# schematic.net
KiCad netlist of a schematic drawn in Altium Designer
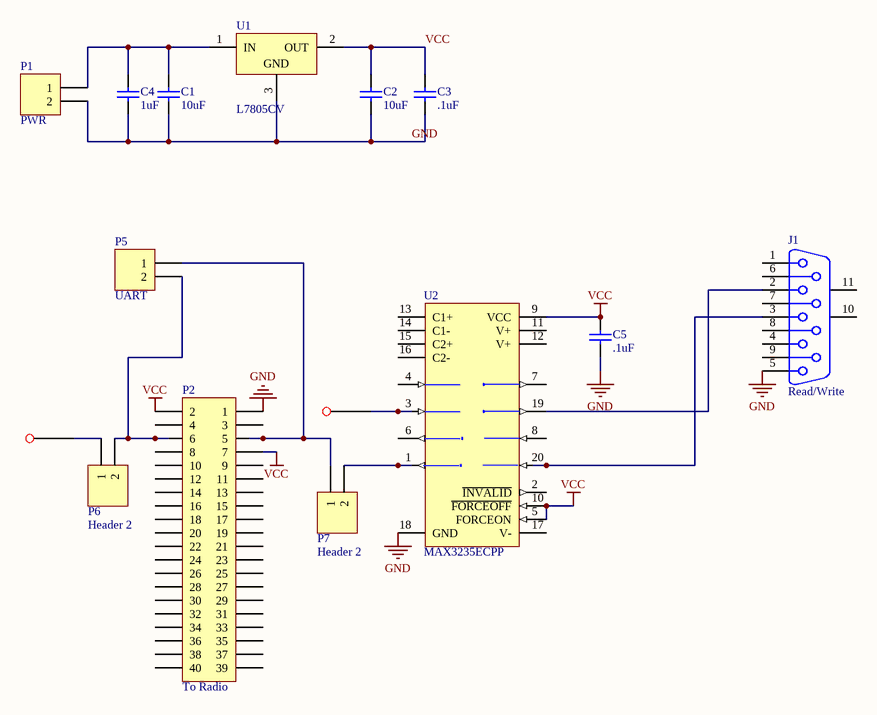
[diagram p0: schematic.SchDoc]

(export (version "E")
  (design (tool "Eeschema 10.0.6"))
  (components
    (comp (ref "C1")
      (value "10uF")
      (footprint "1206")
      (description "Capacitor")
      (fields (field (name "PUBLISHER") "Altium Limited"))
      (libsource (lib "Miscellaneous Devices") (part "Cap"))
    )
    (comp (ref "C2")
      (value "10uF")
      (footprint "1206")
      (description "Capacitor")
      (fields (field (name "PUBLISHER") "Altium Limited"))
      (libsource (lib "Miscellaneous Devices") (part "Cap"))
    )
    (comp (ref "C3")
      (value ".1uF")
      (footprint "1206")
      (description "Capacitor")
      (fields (field (name "PUBLISHER") "Altium Limited"))
      (libsource (lib "Miscellaneous Devices") (part "Cap"))
    )
    (comp (ref "C4")
      (value "1uF")
      (footprint "1206")
      (description "Capacitor")
      (fields (field (name "PUBLISHER") "Altium Limited"))
      (libsource (lib "Miscellaneous Devices") (part "Cap"))
    )
    (comp (ref "C5")
      (value ".1uF")
      (footprint "1206")
      (description "Capacitor")
      (fields (field (name "PUBLISHER") "Altium Limited"))
      (libsource (lib "Miscellaneous Devices") (part "Cap"))
    )
    (comp (ref "J1")
      (value "Read/Write")
      (footprint "DE-9")
      (description "Receptacle Assembly, 9 Position, Right Angle")
      (fields (field (name "PUBLISHER") "Altium Limited"))
      (libsource (lib "Miscellaneous Connectors") (part "D Connector 9"))
    )
    (comp (ref "P1")
      (value "PWR")
      (footprint "Screw Terminal - 2")
      (description "Header, 2-Pin")
      (fields (field (name "PUBLISHER") "Altium Limited"))
      (libsource (lib "Miscellaneous Connectors") (part "Header 2"))
    )
    (comp (ref "P2")
      (value "To Radio")
      (footprint "Header 2x20 2mm r&c pitch")
      (description "Header, 20-Pin, Dual row")
      (fields (field (name "PUBLISHER") "Altium Limited"))
      (libsource (lib "Miscellaneous Connectors") (part "Header 20X2"))
    )
    (comp (ref "P3")
      (value "~")
      (footprint "Solder Pad")
      (description "A pad to solder a wire connection to")
      (libsource (lib "schLib") (part "Solder Pad"))
    )
    (comp (ref "P4")
      (value "~")
      (footprint "Solder Pad")
      (description "A pad to solder a wire connection to")
      (libsource (lib "schLib") (part "Solder Pad"))
    )
    (comp (ref "P5")
      (value "UART")
      (footprint "Screw Terminal - 2")
      (description "Header, 2-Pin")
      (fields (field (name "PUBLISHER") "Altium Limited"))
      (libsource (lib "Miscellaneous Connectors") (part "Header 2"))
    )
    (comp (ref "P6")
      (value "Header 2")
      (footprint "HDR1X2")
      (description "Header, 2-Pin")
      (fields (field (name "PUBLISHER") "Altium Limited"))
      (libsource (lib "") (part "Header 2_1"))
    )
    (comp (ref "P7")
      (value "Header 2")
      (footprint "HDR1X2")
      (description "Header, 2-Pin")
      (fields (field (name "PUBLISHER") "Altium Limited"))
      (libsource (lib "") (part "Header 2_1"))
    )
    (comp (ref "U1")
      (value "L7805CV")
      (footprint "TO220ABN")
      (description "Positive Voltage Regulator")
      (fields (field (name "PUBLISHER") "Altium Limited"))
      (libsource (lib "ST Power Mgt Voltage Regulator") (part "L7805CV"))
    )
    (comp (ref "U2")
      (value "MAX3235ECPP")
      (footprint "PP20")
      (description "±15kV ESD-Protected, 1µA, 250kbps, 5V, Dual RS-232 Transceiver with Internal Capacitor")
      (fields (field (name "PUBLISHER") "Altium Limited"))
      (libsource (lib "Maxim Communication Transceiver") (part "MAX3235ECPP"))
    )
  )
  (nets
    (net (code "1") (name "GND") (class "Default")
      (node (ref "C1") (pin "1") (pinfunction "1_1") (pintype "passive"))
      (node (ref "C2") (pin "1") (pinfunction "1_1") (pintype "passive"))
      (node (ref "C3") (pin "1") (pinfunction "1_1") (pintype "passive"))
      (node (ref "C4") (pin "1") (pinfunction "1_1") (pintype "passive"))
      (node (ref "C5") (pin "1") (pinfunction "1_1") (pintype "passive"))
      (node (ref "J1") (pin "5") (pinfunction "5_5") (pintype "passive"))
      (node (ref "P1") (pin "2") (pinfunction "2_2") (pintype "passive"))
      (node (ref "P2") (pin "1") (pinfunction "1_1") (pintype "passive"))
      (node (ref "U1") (pin "3") (pinfunction "GND_3") (pintype "power_in"))
      (node (ref "U2") (pin "18") (pinfunction "GND_18") (pintype "power_in"))
    )
    (net (code "2") (name "Net-(P2-Pad5)") (class "Default")
      (node (ref "P2") (pin "5") (pinfunction "5_5") (pintype "passive"))
      (node (ref "P5") (pin "1") (pinfunction "1_1") (pintype "passive"))
      (node (ref "P7") (pin "1") (pinfunction "1_1") (pintype "passive"))
    )
    (net (code "3") (name "Net-(P2-Pad6)") (class "Default")
      (node (ref "P2") (pin "6") (pinfunction "6_6") (pintype "passive"))
      (node (ref "P5") (pin "2") (pinfunction "2_2") (pintype "passive"))
      (node (ref "P6") (pin "2") (pinfunction "2_2") (pintype "passive"))
    )
    (net (code "4") (name "Net-(P3-Pad1)") (class "Default")
      (node (ref "P3") (pin "1") (pinfunction "1_1") (pintype "passive"))
      (node (ref "P6") (pin "1") (pinfunction "1_1") (pintype "passive"))
    )
    (net (code "5") (name "Net-(U1-IN)") (class "Default")
      (node (ref "C1") (pin "2") (pinfunction "2_2") (pintype "passive"))
      (node (ref "C4") (pin "2") (pinfunction "2_2") (pintype "passive"))
      (node (ref "P1") (pin "1") (pinfunction "1_1") (pintype "passive"))
      (node (ref "U1") (pin "1") (pinfunction "IN_1") (pintype "power_in"))
    )
    (net (code "6") (name "Net-(U2-R2IN)") (class "Default")
      (node (ref "J1") (pin "3") (pinfunction "3_3") (pintype "passive"))
      (node (ref "U2") (pin "20") (pinfunction "R2IN_20") (pintype "input"))
    )
    (net (code "7") (name "Net-(U2-R2OUT)") (class "Default")
      (node (ref "P7") (pin "2") (pinfunction "2_2") (pintype "passive"))
      (node (ref "U2") (pin "1") (pinfunction "R2OUT_1") (pintype "output"))
    )
    (net (code "8") (name "Net-(U2-T2IN)") (class "Default")
      (node (ref "P4") (pin "1") (pinfunction "1_1") (pintype "passive"))
      (node (ref "U2") (pin "3") (pinfunction "T2IN_3") (pintype "input"))
    )
    (net (code "9") (name "Net-(U2-T2OUT)") (class "Default")
      (node (ref "J1") (pin "2") (pinfunction "2_2") (pintype "passive"))
      (node (ref "U2") (pin "19") (pinfunction "T2OUT_19") (pintype "output"))
    )
    (net (code "10") (name "VCC") (class "Default")
      (node (ref "C2") (pin "2") (pinfunction "2_2") (pintype "passive"))
      (node (ref "C3") (pin "2") (pinfunction "2_2") (pintype "passive"))
      (node (ref "C5") (pin "2") (pinfunction "2_2") (pintype "passive"))
      (node (ref "P2") (pin "2") (pinfunction "2_2") (pintype "passive"))
      (node (ref "P2") (pin "7") (pinfunction "7_7") (pintype "passive"))
      (node (ref "U1") (pin "2") (pinfunction "OUT_2") (pintype "power_in"))
      (node (ref "U2") (pin "10") (pinfunction "~{FORCEOFF}_10") (pintype "input"))
      (node (ref "U2") (pin "5") (pinfunction "FORCEON_5") (pintype "input"))
      (node (ref "U2") (pin "9") (pinfunction "VCC_9") (pintype "power_in"))
    )
    (net (code "11") (name "unconnected-(J1-MH1-Pad10)") (class "Default")
      (node (ref "J1") (pin "10") (pinfunction "MH1_10") (pintype "passive"))
    )
    (net (code "12") (name "unconnected-(J1-MH2-Pad11)") (class "Default")
      (node (ref "J1") (pin "11") (pinfunction "MH2_11") (pintype "passive"))
    )
    (net (code "13") (name "unconnected-(J1-Pad1)") (class "Default")
      (node (ref "J1") (pin "1") (pinfunction "1_1") (pintype "passive"))
    )
    (net (code "14") (name "unconnected-(J1-Pad4)") (class "Default")
      (node (ref "J1") (pin "4") (pinfunction "4_4") (pintype "passive"))
    )
    (net (code "15") (name "unconnected-(J1-Pad6)") (class "Default")
      (node (ref "J1") (pin "6") (pinfunction "6_6") (pintype "passive"))
    )
    (net (code "16") (name "unconnected-(J1-Pad7)") (class "Default")
      (node (ref "J1") (pin "7") (pinfunction "7_7") (pintype "passive"))
    )
    (net (code "17") (name "unconnected-(J1-Pad8)") (class "Default")
      (node (ref "J1") (pin "8") (pinfunction "8_8") (pintype "passive"))
    )
    (net (code "18") (name "unconnected-(J1-Pad9)") (class "Default")
      (node (ref "J1") (pin "9") (pinfunction "9_9") (pintype "passive"))
    )
    (net (code "19") (name "unconnected-(P2-Pad3)") (class "Default")
      (node (ref "P2") (pin "3") (pinfunction "3_3") (pintype "passive"))
    )
    (net (code "20") (name "unconnected-(P2-Pad4)") (class "Default")
      (node (ref "P2") (pin "4") (pinfunction "4_4") (pintype "passive"))
    )
    (net (code "21") (name "unconnected-(P2-Pad8)") (class "Default")
      (node (ref "P2") (pin "8") (pinfunction "8_8") (pintype "passive"))
    )
    (net (code "22") (name "unconnected-(P2-Pad9)") (class "Default")
      (node (ref "P2") (pin "9") (pinfunction "9_9") (pintype "passive"))
    )
    (net (code "23") (name "unconnected-(P2-Pad10)") (class "Default")
      (node (ref "P2") (pin "10") (pinfunction "10_10") (pintype "passive"))
    )
    (net (code "24") (name "unconnected-(P2-Pad11)") (class "Default")
      (node (ref "P2") (pin "11") (pinfunction "11_11") (pintype "passive"))
    )
    (net (code "25") (name "unconnected-(P2-Pad12)") (class "Default")
      (node (ref "P2") (pin "12") (pinfunction "12_12") (pintype "passive"))
    )
    (net (code "26") (name "unconnected-(P2-Pad13)") (class "Default")
      (node (ref "P2") (pin "13") (pinfunction "13_13") (pintype "passive"))
    )
    (net (code "27") (name "unconnected-(P2-Pad14)") (class "Default")
      (node (ref "P2") (pin "14") (pinfunction "14_14") (pintype "passive"))
    )
    (net (code "28") (name "unconnected-(P2-Pad15)") (class "Default")
      (node (ref "P2") (pin "15") (pinfunction "15_15") (pintype "passive"))
    )
    (net (code "29") (name "unconnected-(P2-Pad16)") (class "Default")
      (node (ref "P2") (pin "16") (pinfunction "16_16") (pintype "passive"))
    )
    (net (code "30") (name "unconnected-(P2-Pad17)") (class "Default")
      (node (ref "P2") (pin "17") (pinfunction "17_17") (pintype "passive"))
    )
    (net (code "31") (name "unconnected-(P2-Pad18)") (class "Default")
      (node (ref "P2") (pin "18") (pinfunction "18_18") (pintype "passive"))
    )
    (net (code "32") (name "unconnected-(P2-Pad19)") (class "Default")
      (node (ref "P2") (pin "19") (pinfunction "19_19") (pintype "passive"))
    )
    (net (code "33") (name "unconnected-(P2-Pad20)") (class "Default")
      (node (ref "P2") (pin "20") (pinfunction "20_20") (pintype "passive"))
    )
    (net (code "34") (name "unconnected-(P2-Pad21)") (class "Default")
      (node (ref "P2") (pin "21") (pinfunction "21_21") (pintype "passive"))
    )
    (net (code "35") (name "unconnected-(P2-Pad22)") (class "Default")
      (node (ref "P2") (pin "22") (pinfunction "22_22") (pintype "passive"))
    )
    (net (code "36") (name "unconnected-(P2-Pad23)") (class "Default")
      (node (ref "P2") (pin "23") (pinfunction "23_23") (pintype "passive"))
    )
    (net (code "37") (name "unconnected-(P2-Pad24)") (class "Default")
      (node (ref "P2") (pin "24") (pinfunction "24_24") (pintype "passive"))
    )
    (net (code "38") (name "unconnected-(P2-Pad25)") (class "Default")
      (node (ref "P2") (pin "25") (pinfunction "25_25") (pintype "passive"))
    )
    (net (code "39") (name "unconnected-(P2-Pad26)") (class "Default")
      (node (ref "P2") (pin "26") (pinfunction "26_26") (pintype "passive"))
    )
    (net (code "40") (name "unconnected-(P2-Pad27)") (class "Default")
      (node (ref "P2") (pin "27") (pinfunction "27_27") (pintype "passive"))
    )
    (net (code "41") (name "unconnected-(P2-Pad28)") (class "Default")
      (node (ref "P2") (pin "28") (pinfunction "28_28") (pintype "passive"))
    )
    (net (code "42") (name "unconnected-(P2-Pad29)") (class "Default")
      (node (ref "P2") (pin "29") (pinfunction "29_29") (pintype "passive"))
    )
    (net (code "43") (name "unconnected-(P2-Pad30)") (class "Default")
      (node (ref "P2") (pin "30") (pinfunction "30_30") (pintype "passive"))
    )
    (net (code "44") (name "unconnected-(P2-Pad31)") (class "Default")
      (node (ref "P2") (pin "31") (pinfunction "31_31") (pintype "passive"))
    )
    (net (code "45") (name "unconnected-(P2-Pad32)") (class "Default")
      (node (ref "P2") (pin "32") (pinfunction "32_32") (pintype "passive"))
    )
    (net (code "46") (name "unconnected-(P2-Pad33)") (class "Default")
      (node (ref "P2") (pin "33") (pinfunction "33_33") (pintype "passive"))
    )
    (net (code "47") (name "unconnected-(P2-Pad34)") (class "Default")
      (node (ref "P2") (pin "34") (pinfunction "34_34") (pintype "passive"))
    )
    (net (code "48") (name "unconnected-(P2-Pad35)") (class "Default")
      (node (ref "P2") (pin "35") (pinfunction "35_35") (pintype "passive"))
    )
    (net (code "49") (name "unconnected-(P2-Pad36)") (class "Default")
      (node (ref "P2") (pin "36") (pinfunction "36_36") (pintype "passive"))
    )
    (net (code "50") (name "unconnected-(P2-Pad37)") (class "Default")
      (node (ref "P2") (pin "37") (pinfunction "37_37") (pintype "passive"))
    )
    (net (code "51") (name "unconnected-(P2-Pad38)") (class "Default")
      (node (ref "P2") (pin "38") (pinfunction "38_38") (pintype "passive"))
    )
    (net (code "52") (name "unconnected-(P2-Pad39)") (class "Default")
      (node (ref "P2") (pin "39") (pinfunction "39_39") (pintype "passive"))
    )
    (net (code "53") (name "unconnected-(P2-Pad40)") (class "Default")
      (node (ref "P2") (pin "40") (pinfunction "40_40") (pintype "passive"))
    )
    (net (code "54") (name "unconnected-(U2-C1+-Pad13)") (class "Default")
      (node (ref "U2") (pin "13") (pinfunction "C1+_13") (pintype "passive"))
    )
    (net (code "55") (name "unconnected-(U2-C1--Pad14)") (class "Default")
      (node (ref "U2") (pin "14") (pinfunction "C1-_14") (pintype "passive"))
    )
    (net (code "56") (name "unconnected-(U2-C2+-Pad15)") (class "Default")
      (node (ref "U2") (pin "15") (pinfunction "C2+_15") (pintype "passive"))
    )
    (net (code "57") (name "unconnected-(U2-C2--Pad16)") (class "Default")
      (node (ref "U2") (pin "16") (pinfunction "C2-_16") (pintype "passive"))
    )
    (net (code "58") (name "unconnected-(U2-R1IN-Pad8)") (class "Default")
      (node (ref "U2") (pin "8") (pinfunction "R1IN_8") (pintype "input"))
    )
    (net (code "59") (name "unconnected-(U2-R1OUT-Pad6)") (class "Default")
      (node (ref "U2") (pin "6") (pinfunction "R1OUT_6") (pintype "output"))
    )
    (net (code "60") (name "unconnected-(U2-T1IN-Pad4)") (class "Default")
      (node (ref "U2") (pin "4") (pinfunction "T1IN_4") (pintype "input"))
    )
    (net (code "61") (name "unconnected-(U2-T1OUT-Pad7)") (class "Default")
      (node (ref "U2") (pin "7") (pinfunction "T1OUT_7") (pintype "output"))
    )
    (net (code "62") (name "unconnected-(U2-V+-Pad11)") (class "Default")
      (node (ref "U2") (pin "11") (pinfunction "V+_11") (pintype "power_in"))
    )
    (net (code "63") (name "unconnected-(U2-V+-Pad12)") (class "Default")
      (node (ref "U2") (pin "12") (pinfunction "V+_12") (pintype "power_in"))
    )
    (net (code "64") (name "unconnected-(U2-V--Pad17)") (class "Default")
      (node (ref "U2") (pin "17") (pinfunction "V-_17") (pintype "power_in"))
    )
    (net (code "65") (name "unconnected-(U2-~{INVALID}-Pad2)") (class "Default")
      (node (ref "U2") (pin "2") (pinfunction "~{INVALID}_2") (pintype "output"))
    )
  )
)
